# POWER.net
KiCad netlist of a schematic drawn in Altium Designer
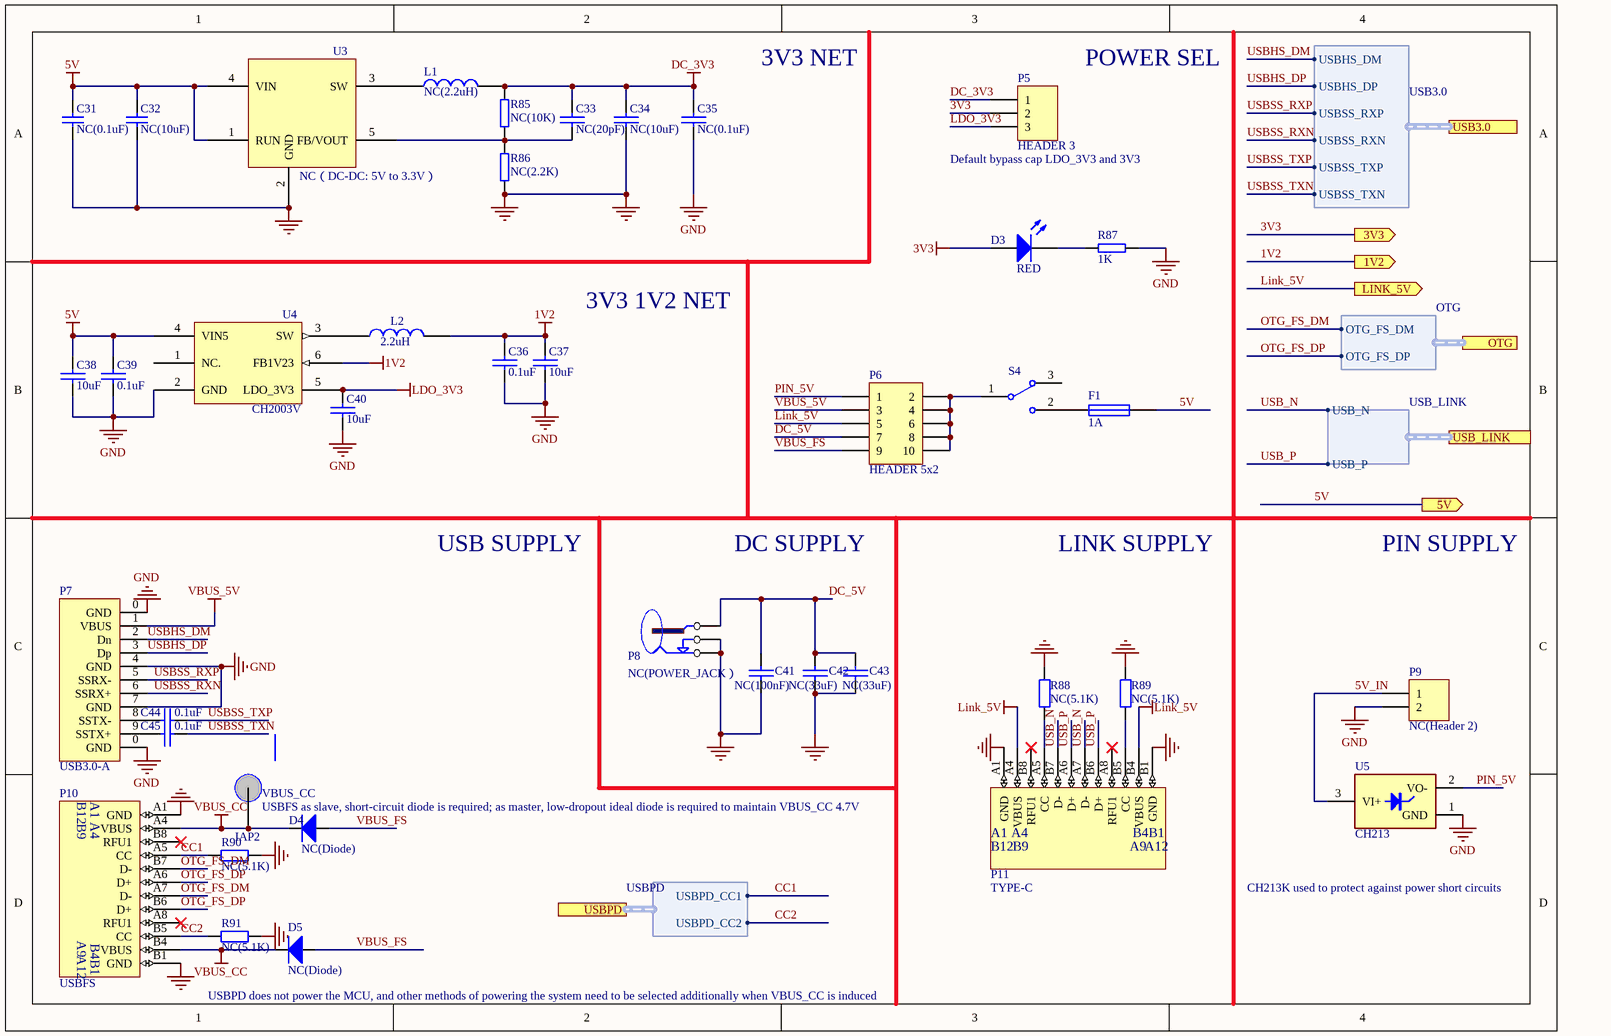
[diagram p0: POWER.SchDoc]

(export (version "E")
  (design (tool "Eeschema 10.0.6"))
  (components
    (comp (ref "C31")
      (value "NC(0.1uF)")
      (footprint "0402_C")
      (description "Capacitor")
      (fields (field (name "PUBLISHER") "Altium Limited"))
      (libsource (lib "Miscellaneous Devices") (part "Cap"))
    )
    (comp (ref "C32")
      (value "NC(10uF)")
      (footprint "0603_C")
      (description "Capacitor")
      (fields (field (name "PUBLISHER") "Altium Limited"))
      (libsource (lib "Miscellaneous Devices") (part "Cap"))
    )
    (comp (ref "C33")
      (value "NC(20pF)")
      (footprint "0402_C")
      (description "Capacitor")
      (libsource (lib "*") (part "CAP"))
    )
    (comp (ref "C34")
      (value "NC(10uF)")
      (footprint "0603_C")
      (description "Capacitor")
      (libsource (lib "*") (part "CAP"))
    )
    (comp (ref "C35")
      (value "NC(0.1uF)")
      (footprint "0402_C")
      (description "Capacitor")
      (libsource (lib "*") (part "CAP"))
    )
    (comp (ref "C36")
      (value "0.1uF")
      (footprint "0402_C")
      (description "Capacitor")
      (libsource (lib "") (part "CAP_1"))
    )
    (comp (ref "C37")
      (value "10uF")
      (footprint "0603_C")
      (description "Capacitor")
      (libsource (lib "*") (part "CAP"))
    )
    (comp (ref "C38")
      (value "10uF")
      (footprint "0603_C")
      (description "Capacitor")
      (libsource (lib "*") (part "CAP"))
    )
    (comp (ref "C39")
      (value "0.1uF")
      (footprint "0402_C")
      (description "Capacitor")
      (libsource (lib "") (part "CAP_1"))
    )
    (comp (ref "C40")
      (value "10uF")
      (footprint "0603_C")
      (description "Capacitor")
      (libsource (lib "*") (part "CAP"))
    )
    (comp (ref "C41")
      (value "NC(100nF)")
      (footprint "0402_C")
      (description "Capacitor")
      (libsource (lib "*") (part "CAP"))
    )
    (comp (ref "C42")
      (value "NC(33uF)")
      (footprint "3528_C")
      (description "Capacitor")
      (libsource (lib "*") (part "CAP"))
    )
    (comp (ref "C43")
      (value "NC(33uF)")
      (footprint "3528_C")
      (description "Capacitor")
      (libsource (lib "*") (part "CAP"))
    )
    (comp (ref "C44")
      (value "0.1uF")
      (footprint "0402_C")
      (description "Capacitor")
      (libsource (lib "*") (part "CAP"))
    )
    (comp (ref "C45")
      (value "0.1uF")
      (footprint "0402_C")
      (description "Capacitor")
      (libsource (lib "*") (part "CAP"))
    )
    (comp (ref "D3")
      (value "RED")
      (footprint "0603+")
      (description "Typical INFRARED GaAs LED")
      (fields (field (name "PUBLISHER") "Altium Limited"))
      (libsource (lib "*") (part "LED0"))
    )
    (comp (ref "D4")
      (value "NC(Diode)")
      (footprint "SOD-323")
      (description "Default Diode")
      (libsource (lib "wch_sch_others") (part "Diode"))
    )
    (comp (ref "D5")
      (value "NC(Diode)")
      (footprint "SOD-323")
      (description "Default Diode")
      (libsource (lib "wch_sch_others") (part "Diode"))
    )
    (comp (ref "F1")
      (value "1A")
      (footprint "0805")
      (description "Fuse")
      (libsource (lib "*") (part "FUSE1"))
    )
    (comp (ref "IAP2")
      (value "VBUS_CC")
      (footprint "TESTPOINT1")
      (description "测试点")
      (libsource (lib "wch_sch_others") (part "Testpoint"))
    )
    (comp (ref "L1") (value "NC(2.2uH)") (footprint "CD32") (libsource (lib "*") (part "INDUCTOR")))
    (comp (ref "L2") (value "2.2uH") (footprint "CD32") (libsource (lib "*") (part "INDUCTOR")))
    (comp (ref "P5")
      (value "HEADER 3")
      (footprint "SIP3-2.54MM")
      (description "Header, 3-Pin")
      (libsource (lib "wch_sch_others") (part "HEADER 3"))
    )
    (comp (ref "P6")
      (value "HEADER 5x2")
      (footprint "MYPCB:IDC10-2.54mm")
      (description "Header, 5-Pin, Dual row")
      (libsource (lib "wch_sch_others") (part "HEADER 5x2"))
    )
    (comp (ref "P7")
      (value "USB3.0-A")
      (footprint "USB3.0-A-Receptacle")
      (libsource (lib "wch_sch_others") (part "USB3.0-A"))
    )
    (comp (ref "P8") (value "NC(POWER_JACK）") (footprint "DC-005") (libsource (lib "*") (part "POWER_JACK")))
    (comp (ref "P9")
      (value "NC(Header 2)")
      (footprint "SIP2-2.54mm")
      (description "Header, 2-Pin")
      (fields (field (name "PUBLISHER") "Altium Limited"))
      (libsource (lib "*") (part "Header 2"))
    )
    (comp (ref "P10")
      (value "USBFS")
      (footprint "TYPE-C-Receptacle-2.0")
      (libsource (lib "") (part "TYPE-C1_1"))
    )
    (comp (ref "P11")
      (value "TYPE-C")
      (footprint "TYPE-C-Receptacle-2.0")
      (libsource (lib "*") (part "TYPE-C1"))
    )
    (comp (ref "R85") (value "NC(10K)") (footprint "0402") (libsource (lib "*") (part "R")))
    (comp (ref "R86") (value "NC(2.2K)") (footprint "0402") (libsource (lib "*") (part "R")))
    (comp (ref "R87") (value "1K") (footprint "0402") (libsource (lib "wch_sch_others") (part "RES")))
    (comp (ref "R88")
      (value "NC(5.1K)")
      (footprint "0402")
      (description "Resistor")
      (libsource (lib "") (part "Res2_1"))
    )
    (comp (ref "R89")
      (value "NC(5.1K)")
      (footprint "0402")
      (description "Resistor")
      (libsource (lib "") (part "Res2_1"))
    )
    (comp (ref "R90")
      (value "NC(5.1K)")
      (footprint "0402")
      (description "Resistor")
      (libsource (lib "Miscellaneous Devices") (part "Res2"))
    )
    (comp (ref "R91")
      (value "NC(5.1K)")
      (footprint "0402")
      (description "Resistor")
      (libsource (lib "Miscellaneous Devices") (part "Res2"))
    )
    (comp (ref "S4")
      (value "SW-SPDT")
      (footprint "SW1")
      (description "SPDT Subminiature Toggle Switch, Right Angle Mounting, Vertical Actuation")
      (libsource (lib "*") (part "SW-SPDT"))
    )
    (comp (ref "U3")
      (value "NC（DC-DC: 5V to 3.3V）")
      (footprint "SOT-23-5")
      (libsource (lib "SCH") (part "8503AM"))
    )
    (comp (ref "U4")
      (value "CH2003V")
      (footprint "SOT-23-6")
      (description "Step-Down DC-DC Converter, 5V input, 1.23V * 700mA output, with LDO 3.3V * 160mA")
      (libsource (lib "DHXXXSCH") (part "CH2003V"))
    )
    (comp (ref "U5")
      (value "CH213")
      (footprint "SOT-23-3")
      (description "Ideal Diode 5V*1A")
      (libsource (lib "CHXXX") (part "CH213E"))
    )
  )
  (nets
    (net (code "5") (name "/5V_IN") (class "Default")
      (node (ref "P9") (pin "1") (pinfunction "1_1") (pintype "passive"))
      (node (ref "U5") (pin "3") (pinfunction "VI+_3") (pintype "power_in"))
    )
    (net (code "6") (name "/CC1") (class "Default")
      (node (ref "P10") (pin "A5") (pinfunction "CC_A5") (pintype "bidirectional"))
      (node (ref "R90") (pin "1") (pinfunction "1_1") (pintype "passive"))
    )
    (net (code "7") (name "/CC2") (class "Default")
      (node (ref "P10") (pin "B5") (pinfunction "CC_B5") (pintype "bidirectional"))
      (node (ref "R91") (pin "1") (pinfunction "1_1") (pintype "passive"))
    )
    (net (code "8") (name "/DC_5V") (class "Default")
      (node (ref "C41") (pin "2") (pinfunction "2_2") (pintype "passive"))
      (node (ref "C42") (pin "2") (pinfunction "2_2") (pintype "passive"))
      (node (ref "C43") (pin "2") (pinfunction "2_2") (pintype "passive"))
      (node (ref "P6") (pin "7") (pinfunction "7_7") (pintype "passive"))
      (node (ref "P8") (pin "1") (pinfunction "V_1") (pintype "passive"))
    )
    (net (code "9") (name "/OTG_FS_DM") (class "Default")
      (node (ref "P10") (pin "A7") (pinfunction "D-_A7") (pintype "bidirectional"))
      (node (ref "P10") (pin "B7") (pinfunction "D-_B7") (pintype "bidirectional"))
    )
    (net (code "10") (name "/OTG_FS_DP") (class "Default")
      (node (ref "P10") (pin "A6") (pinfunction "D+_A6") (pintype "bidirectional"))
      (node (ref "P10") (pin "B6") (pinfunction "D+_B6") (pintype "bidirectional"))
    )
    (net (code "11") (name "/PIN_5V") (class "Default")
      (node (ref "P6") (pin "1") (pinfunction "1_1") (pintype "passive"))
      (node (ref "U5") (pin "2") (pinfunction "VO-_2") (pintype "power_in"))
    )
    (net (code "12") (name "/USBHS_DM") (class "Default")
      (node (ref "P7") (pin "2") (pinfunction "Dn_2") (pintype "passive"))
    )
    (net (code "13") (name "/USBHS_DP") (class "Default")
      (node (ref "P7") (pin "3") (pinfunction "Dp_3") (pintype "passive"))
    )
    (net (code "14") (name "/USBSS_RXN") (class "Default")
      (node (ref "P7") (pin "6") (pinfunction "SSRX+_6") (pintype "passive"))
    )
    (net (code "15") (name "/USBSS_RXP") (class "Default")
      (node (ref "P7") (pin "5") (pinfunction "SSRX-_5") (pintype "passive"))
    )
    (net (code "16") (name "/USBSS_TXN") (class "Default")
      (node (ref "C45") (pin "2") (pinfunction "2_2") (pintype "passive"))
    )
    (net (code "17") (name "/USBSS_TXP") (class "Default")
      (node (ref "C44") (pin "2") (pinfunction "2_2") (pintype "passive"))
    )
    (net (code "18") (name "/USB_N") (class "Default")
      (node (ref "P11") (pin "A7") (pinfunction "D-_A7") (pintype "bidirectional"))
      (node (ref "P11") (pin "B7") (pinfunction "D-_B7") (pintype "bidirectional"))
    )
    (net (code "19") (name "/USB_P") (class "Default")
      (node (ref "P11") (pin "A6") (pinfunction "D+_A6") (pintype "bidirectional"))
      (node (ref "P11") (pin "B6") (pinfunction "D+_B6") (pintype "bidirectional"))
    )
    (net (code "20") (name "/VBUS_FS") (class "Default")
      (node (ref "D4") (pin "1") (pinfunction "A_1") (pintype "passive"))
      (node (ref "D5") (pin "1") (pinfunction "A_1") (pintype "passive"))
      (node (ref "P6") (pin "9") (pinfunction "9_9") (pintype "passive"))
    )
    (net (code "25") (name "1V2") (class "Default")
      (node (ref "C36") (pin "2") (pinfunction "2_2") (pintype "passive"))
      (node (ref "C37") (pin "2") (pinfunction "2_2") (pintype "passive"))
      (node (ref "L2") (pin "2") (pinfunction "2_2") (pintype "passive"))
      (node (ref "U4") (pin "6") (pinfunction "FB1V23_6") (pintype "input"))
    )
    (net (code "26") (name "3V3") (class "Default")
      (node (ref "D3") (pin "1") (pinfunction "A_1") (pintype "passive"))
      (node (ref "P5") (pin "2") (pinfunction "2_2") (pintype "passive"))
    )
    (net (code "27") (name "5V") (class "Default")
      (node (ref "C31") (pin "2") (pinfunction "2_2") (pintype "passive"))
      (node (ref "C32") (pin "2") (pinfunction "2_2") (pintype "passive"))
      (node (ref "C38") (pin "2") (pinfunction "2_2") (pintype "passive"))
      (node (ref "C39") (pin "2") (pinfunction "2_2") (pintype "passive"))
      (node (ref "F1") (pin "1") (pinfunction "1_1") (pintype "passive"))
      (node (ref "U3") (pin "1") (pinfunction "RUN_1") (pintype "passive"))
      (node (ref "U3") (pin "4") (pinfunction "VIN_4") (pintype "passive"))
      (node (ref "U4") (pin "4") (pinfunction "VIN5_4") (pintype "power_in"))
    )
    (net (code "28") (name "DC_3V3") (class "Default")
      (node (ref "C33") (pin "1") (pinfunction "1_1") (pintype "passive"))
      (node (ref "C34") (pin "1") (pinfunction "1_1") (pintype "passive"))
      (node (ref "C35") (pin "1") (pinfunction "1_1") (pintype "passive"))
      (node (ref "L1") (pin "2") (pinfunction "2_2") (pintype "passive"))
      (node (ref "P5") (pin "1") (pinfunction "1_1") (pintype "passive"))
      (node (ref "R85") (pin "1") (pinfunction "1_1") (pintype "passive"))
    )
    (net (code "29") (name "GND") (class "Default")
      (node (ref "C31") (pin "1") (pinfunction "1_1") (pintype "passive"))
      (node (ref "C32") (pin "1") (pinfunction "1_1") (pintype "passive"))
      (node (ref "C34") (pin "2") (pinfunction "2_2") (pintype "passive"))
      (node (ref "C35") (pin "2") (pinfunction "2_2") (pintype "passive"))
      (node (ref "C36") (pin "1") (pinfunction "1_1") (pintype "passive"))
      (node (ref "C37") (pin "1") (pinfunction "1_1") (pintype "passive"))
      (node (ref "C38") (pin "1") (pinfunction "1_1") (pintype "passive"))
      (node (ref "C39") (pin "1") (pinfunction "1_1") (pintype "passive"))
      (node (ref "C40") (pin "1") (pinfunction "1_1") (pintype "passive"))
      (node (ref "C41") (pin "1") (pinfunction "1_1") (pintype "passive"))
      (node (ref "C42") (pin "1") (pinfunction "1_1") (pintype "passive"))
      (node (ref "C43") (pin "1") (pinfunction "1_1") (pintype "passive"))
      (node (ref "P10") (pin "A1") (pinfunction "GND_A1") (pintype "bidirectional"))
      (node (ref "P10") (pin "B1") (pinfunction "GND_B1") (pintype "bidirectional"))
      (node (ref "P11") (pin "A1") (pinfunction "GND_A1") (pintype "bidirectional"))
      (node (ref "P11") (pin "B1") (pinfunction "GND_B1") (pintype "bidirectional"))
      (node (ref "P7") (pin "0") (pinfunction "GND_0") (pintype "passive"))
      (node (ref "P7") (pin "4") (pinfunction "GND_4") (pintype "passive"))
      (node (ref "P7") (pin "7") (pinfunction "GND_7") (pintype "passive"))
      (node (ref "P8") (pin "2") (pinfunction "G_2") (pintype "passive"))
      (node (ref "P8") (pin "3") (pinfunction "X_3") (pintype "passive"))
      (node (ref "P9") (pin "2") (pinfunction "2_2") (pintype "passive"))
      (node (ref "R86") (pin "1") (pinfunction "1_1") (pintype "passive"))
      (node (ref "R87") (pin "2") (pintype "passive"))
      (node (ref "R88") (pin "2") (pinfunction "2_2") (pintype "passive"))
      (node (ref "R89") (pin "2") (pinfunction "2_2") (pintype "passive"))
      (node (ref "R90") (pin "2") (pinfunction "2_2") (pintype "passive"))
      (node (ref "R91") (pin "2") (pinfunction "2_2") (pintype "passive"))
      (node (ref "U3") (pin "2") (pinfunction "GND_2") (pintype "passive"))
      (node (ref "U4") (pin "2") (pinfunction "GND_2") (pintype "power_in"))
      (node (ref "U5") (pin "1") (pinfunction "GND_1") (pintype "power_in"))
    )
    (net (code "30") (name "LDO_3V3") (class "Default")
      (node (ref "C40") (pin "2") (pinfunction "2_2") (pintype "passive"))
      (node (ref "P5") (pin "3") (pinfunction "3_3") (pintype "passive"))
      (node (ref "U4") (pin "5") (pinfunction "LDO_3V3_5") (pintype "power_in"))
    )
    (net (code "31") (name "Link_5V") (class "Default")
      (node (ref "P11") (pin "A4") (pinfunction "VBUS_A4") (pintype "bidirectional"))
      (node (ref "P11") (pin "B4") (pinfunction "VBUS_B4") (pintype "bidirectional"))
      (node (ref "P6") (pin "5") (pinfunction "5_5") (pintype "passive"))
    )
    (net (code "32") (name "Net-(D3-K)") (class "Default")
      (node (ref "D3") (pin "2") (pinfunction "K_2") (pintype "passive"))
      (node (ref "R87") (pin "1") (pintype "passive"))
    )
    (net (code "33") (name "Net-(F1-Pad2)") (class "Default")
      (node (ref "F1") (pin "2") (pinfunction "2_2") (pintype "passive"))
      (node (ref "S4") (pin "2") (pinfunction "2_2") (pintype "passive"))
    )
    (net (code "34") (name "Net-(P6-Pad10)") (class "Default")
      (node (ref "P6") (pin "10") (pinfunction "10_10") (pintype "passive"))
      (node (ref "P6") (pin "2") (pinfunction "2_2") (pintype "passive"))
      (node (ref "P6") (pin "4") (pinfunction "4_4") (pintype "passive"))
      (node (ref "P6") (pin "6") (pinfunction "6_6") (pintype "passive"))
      (node (ref "P6") (pin "8") (pinfunction "8_8") (pintype "passive"))
      (node (ref "S4") (pin "1") (pinfunction "1_1") (pintype "passive"))
    )
    (net (code "35") (name "Net-(P7-SSTX+)") (class "Default")
      (node (ref "C45") (pin "1") (pinfunction "1_1") (pintype "passive"))
      (node (ref "P7") (pin "9") (pinfunction "SSTX+_9") (pintype "passive"))
    )
    (net (code "36") (name "Net-(P7-SSTX-)") (class "Default")
      (node (ref "C44") (pin "1") (pinfunction "1_1") (pintype "passive"))
      (node (ref "P7") (pin "8") (pinfunction "SSTX-_8") (pintype "passive"))
    )
    (net (code "37") (name "Net-(P11-CC-PadA5)") (class "Default")
      (node (ref "P11") (pin "A5") (pinfunction "CC_A5") (pintype "bidirectional"))
      (node (ref "R88") (pin "1") (pinfunction "1_1") (pintype "passive"))
    )
    (net (code "38") (name "Net-(P11-CC-PadB5)") (class "Default")
      (node (ref "P11") (pin "B5") (pinfunction "CC_B5") (pintype "bidirectional"))
      (node (ref "R89") (pin "1") (pinfunction "1_1") (pintype "passive"))
    )
    (net (code "39") (name "Net-(U3-FB{slash}VOUT)") (class "Default")
      (node (ref "C33") (pin "2") (pinfunction "2_2") (pintype "passive"))
      (node (ref "R85") (pin "2") (pinfunction "2_2") (pintype "passive"))
      (node (ref "R86") (pin "2") (pinfunction "2_2") (pintype "passive"))
      (node (ref "U3") (pin "5") (pinfunction "FB/VOUT_5") (pintype "passive"))
    )
    (net (code "40") (name "Net-(U3-SW)") (class "Default")
      (node (ref "L1") (pin "1") (pinfunction "1_1") (pintype "passive"))
      (node (ref "U3") (pin "3") (pinfunction "SW_3") (pintype "passive"))
    )
    (net (code "41") (name "Net-(U4-SW)") (class "Default")
      (node (ref "L2") (pin "1") (pinfunction "1_1") (pintype "passive"))
      (node (ref "U4") (pin "3") (pinfunction "SW_3") (pintype "output"))
    )
    (net (code "42") (name "VBUS_5V") (class "Default")
      (node (ref "P6") (pin "3") (pinfunction "3_3") (pintype "passive"))
      (node (ref "P7") (pin "1") (pinfunction "VBUS_1") (pintype "passive"))
    )
    (net (code "43") (name "VBUS_CC") (class "Default")
      (node (ref "D4") (pin "2") (pinfunction "K_2") (pintype "passive"))
      (node (ref "D5") (pin "2") (pinfunction "K_2") (pintype "passive"))
      (node (ref "IAP2") (pin "1") (pinfunction "point_1") (pintype "passive"))
      (node (ref "P10") (pin "A4") (pinfunction "VBUS_A4") (pintype "bidirectional"))
      (node (ref "P10") (pin "B4") (pinfunction "VBUS_B4") (pintype "bidirectional"))
    )
    (net (code "44") (name "unconnected-(P10-RFU1-PadA8)") (class "Default")
      (node (ref "P10") (pin "A8") (pinfunction "RFU1_A8") (pintype "bidirectional+no_connect"))
    )
    (net (code "45") (name "unconnected-(P10-RFU1-PadB8)") (class "Default")
      (node (ref "P10") (pin "B8") (pinfunction "RFU1_B8") (pintype "bidirectional+no_connect"))
    )
    (net (code "46") (name "unconnected-(P11-RFU1-PadA8)") (class "Default")
      (node (ref "P11") (pin "A8") (pinfunction "RFU1_A8") (pintype "bidirectional+no_connect"))
    )
    (net (code "47") (name "unconnected-(P11-RFU1-PadB8)") (class "Default")
      (node (ref "P11") (pin "B8") (pinfunction "RFU1_B8") (pintype "bidirectional+no_connect"))
    )
    (net (code "48") (name "unconnected-(S4-Pad3)") (class "Default")
      (node (ref "S4") (pin "3") (pinfunction "3_3") (pintype "passive"))
    )
    (net (code "49") (name "unconnected-(U4-NC.-Pad1)") (class "Default")
      (node (ref "U4") (pin "1") (pinfunction "NC._1") (pintype "passive"))
    )
  )
)
